# ASCII_06_LMS7002M_RF2.net
KiCad netlist of a schematic drawn in Altium Designer
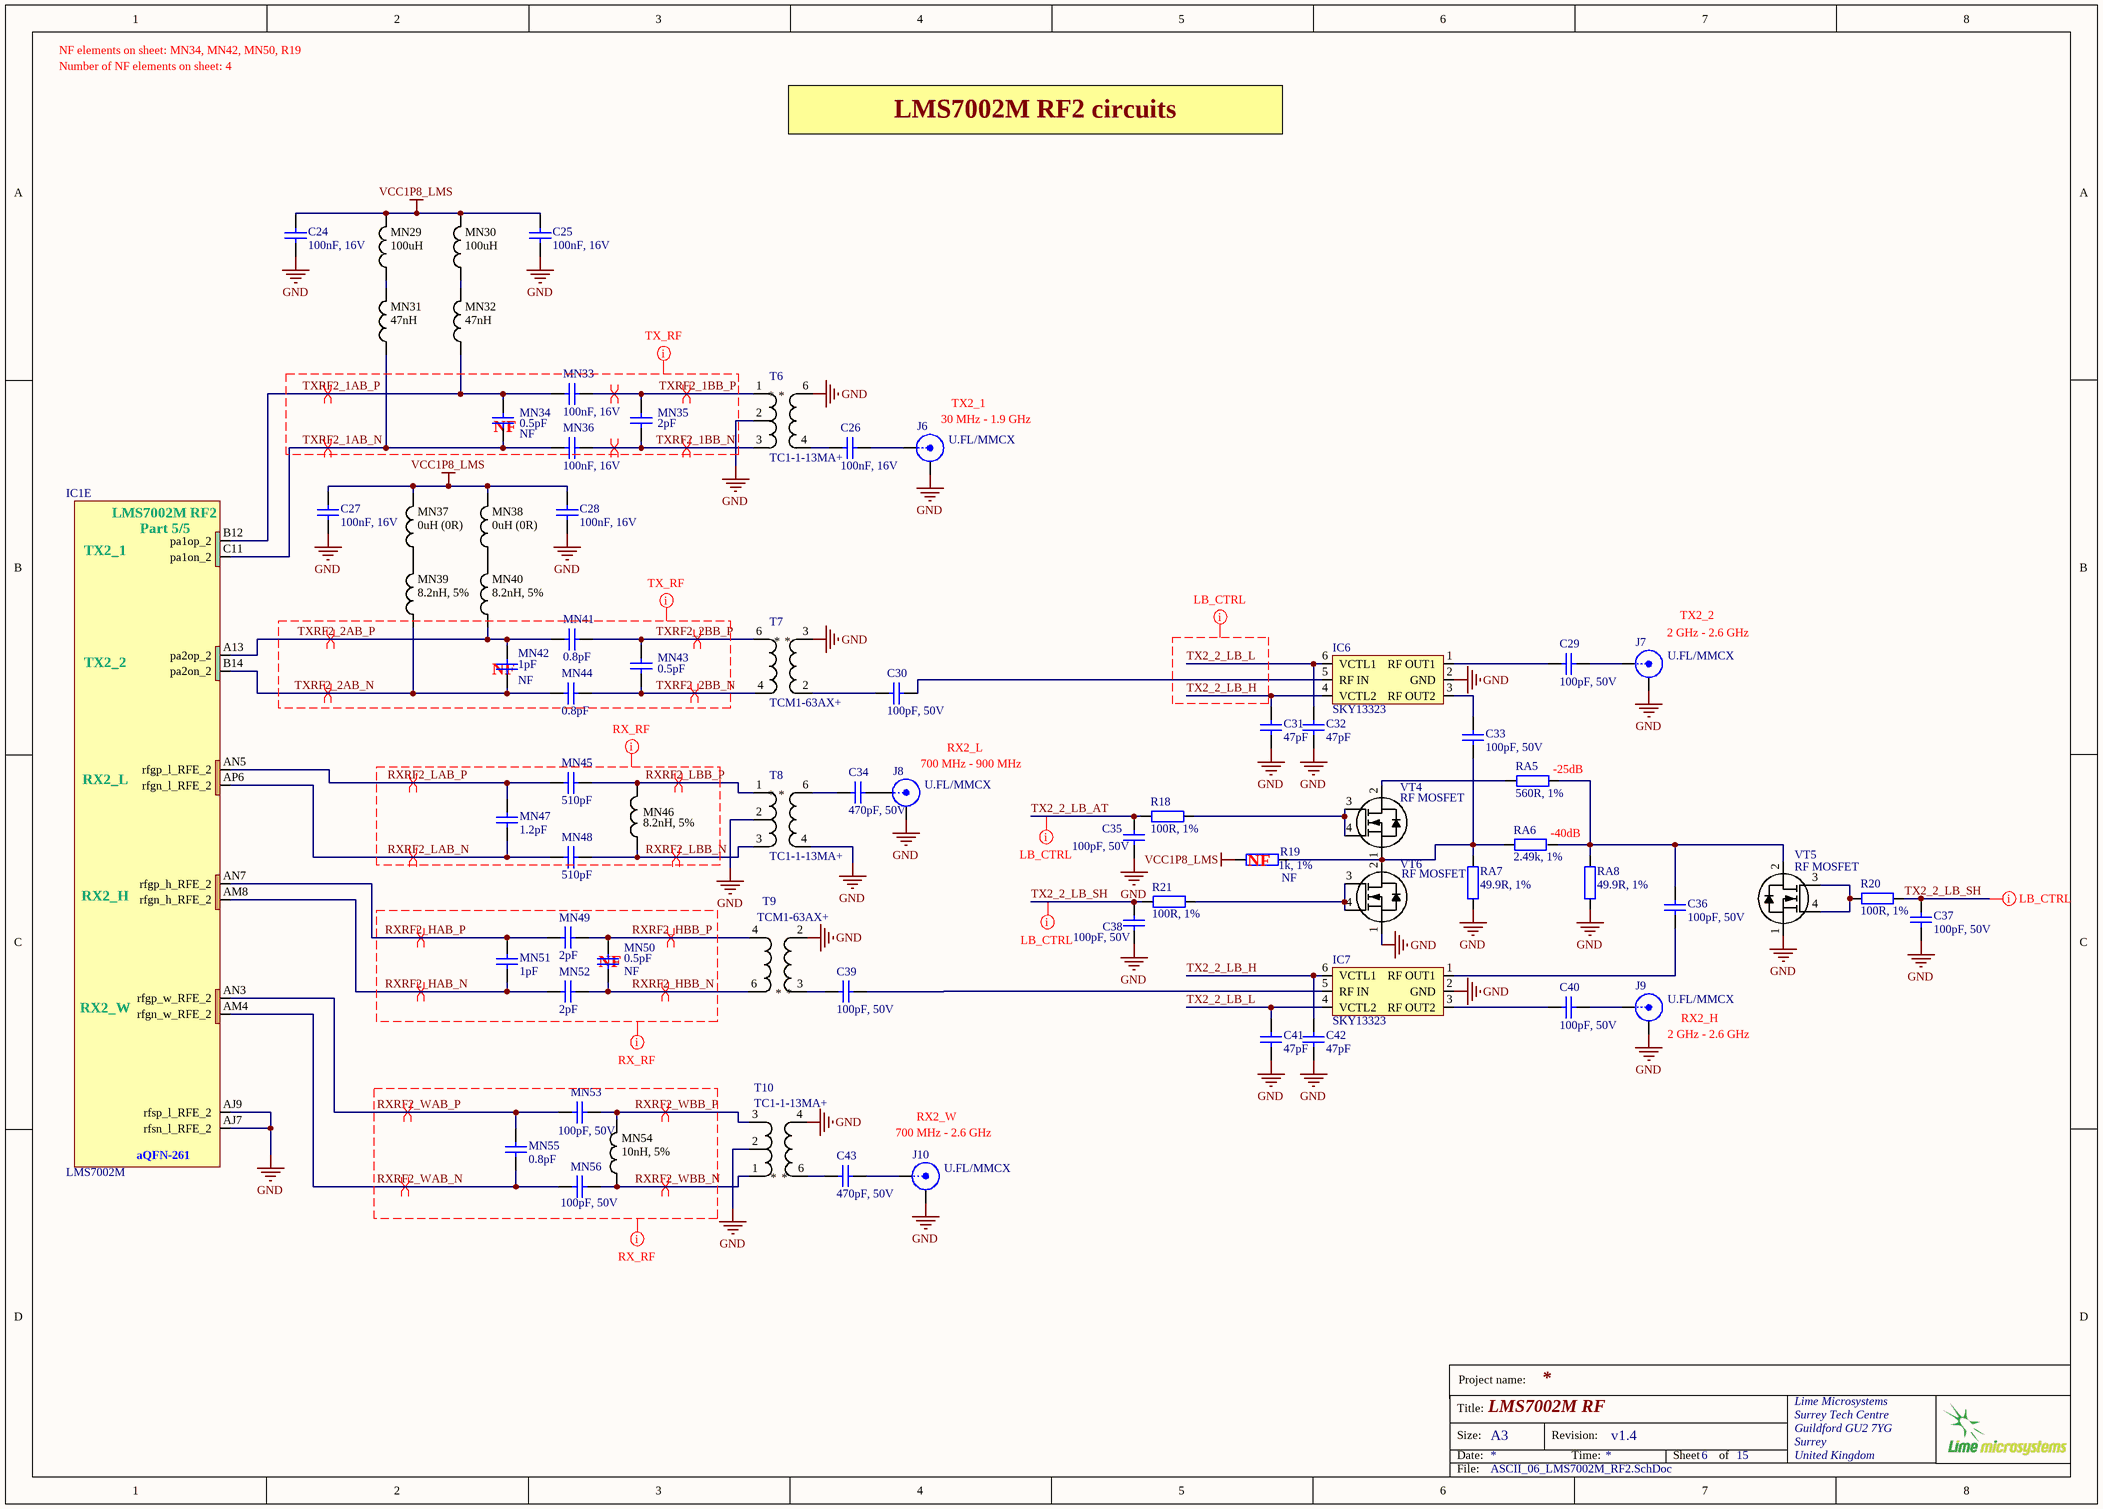
[diagram p0: ASCII_06_LMS7002M_RF2.SchDoc]

(export (version "E")
  (design (tool "Eeschema 10.0.6"))
  (components
    (comp (ref "C24")
      (value "100nF, 16V")
      (footprint "CAP0402")
      (fields
        (field (name "MANUFACTURER") "Murata Electronics")
        (field (name "TOLERANCE") "10 %")
        (field (name "MANUFACTURER PART NUMBER") "GRM155R71C104KA88D")
      )
      (libsource (lib "LimeMicroAltiumLib_schLib") (part "Cap_0402"))
    )
    (comp (ref "C25")
      (value "100nF, 16V")
      (footprint "CAP0402")
      (fields
        (field (name "MANUFACTURER") "Murata Electronics")
        (field (name "TOLERANCE") "10 %")
        (field (name "MANUFACTURER PART NUMBER") "GRM155R71C104KA88D")
      )
      (libsource (lib "LimeMicroAltiumLib_schLib") (part "Cap_0402"))
    )
    (comp (ref "C26")
      (value "100nF, 16V")
      (footprint "CAP0402")
      (fields
        (field (name "MANUFACTURER") "Murata Electronics")
        (field (name "TOLERANCE") "10 %")
        (field (name "MANUFACTURER PART NUMBER") "GRM155R71C104KA88D")
      )
      (libsource (lib "LimeMicroAltiumLib_schLib") (part "Cap_0402"))
    )
    (comp (ref "C27")
      (value "100nF, 16V")
      (footprint "CAP0402")
      (fields
        (field (name "MANUFACTURER") "Murata Electronics")
        (field (name "TOLERANCE") "10 %")
        (field (name "MANUFACTURER PART NUMBER") "GRM155R71C104KA88D")
      )
      (libsource (lib "LimeMicroAltiumLib_schLib") (part "Cap_0402"))
    )
    (comp (ref "C28")
      (value "100nF, 16V")
      (footprint "CAP0402")
      (fields
        (field (name "MANUFACTURER") "Murata Electronics")
        (field (name "TOLERANCE") "10 %")
        (field (name "MANUFACTURER PART NUMBER") "GRM155R71C104KA88D")
      )
      (libsource (lib "LimeMicroAltiumLib_schLib") (part "Cap_0402"))
    )
    (comp (ref "C29")
      (value "100pF, 50V")
      (footprint "CAP0402")
      (fields (field (name "TOLERANCE") "±5%") (field (name "MANUFACTURER") "Yageo"))
      (libsource (lib "LimeMicroAltiumLib_schLib") (part "Cap_0402"))
    )
    (comp (ref "C30")
      (value "100pF, 50V")
      (footprint "CAP0402")
      (fields (field (name "TOLERANCE") "±5%") (field (name "MANUFACTURER") "Yageo"))
      (libsource (lib "LimeMicroAltiumLib_schLib") (part "Cap_0402"))
    )
    (comp (ref "C31")
      (value "47pF")
      (footprint "CAP0402")
      (fields (field (name "TOLERANCE") "±1%") (field (name "MANUFACTURER") "TDK Corporation"))
      (libsource (lib "LimeMicroAltiumLib_schLib") (part "Cap_0402"))
    )
    (comp (ref "C32")
      (value "47pF")
      (footprint "CAP0402")
      (fields (field (name "TOLERANCE") "±1%") (field (name "MANUFACTURER") "TDK Corporation"))
      (libsource (lib "LimeMicroAltiumLib_schLib") (part "Cap_0402"))
    )
    (comp (ref "C33")
      (value "100pF, 50V")
      (footprint "CAP0402")
      (fields (field (name "TOLERANCE") "±5%") (field (name "MANUFACTURER") "Yageo"))
      (libsource (lib "LimeMicroAltiumLib_schLib") (part "Cap_0402"))
    )
    (comp (ref "C34")
      (value "470pF, 50V")
      (footprint "CAP0402")
      (fields
        (field (name "MANUFACTURER PART NUMBER") "C1005C0G1H471J050BA")
        (field (name "TOLERANCE") "±5%")
        (field (name "MANUFACTURER") "TDK Corporation")
      )
      (libsource (lib "LimeMicroAltiumLib_schLib") (part "Cap_0402"))
    )
    (comp (ref "C35")
      (value "100pF, 50V")
      (footprint "CAP0402")
      (fields (field (name "TOLERANCE") "±5%") (field (name "MANUFACTURER") "Yageo"))
      (libsource (lib "LimeMicroAltiumLib_schLib") (part "Cap_0402"))
    )
    (comp (ref "C36")
      (value "100pF, 50V")
      (footprint "CAP0402")
      (fields (field (name "TOLERANCE") "±5%") (field (name "MANUFACTURER") "Yageo"))
      (libsource (lib "LimeMicroAltiumLib_schLib") (part "Cap_0402"))
    )
    (comp (ref "C37")
      (value "100pF, 50V")
      (footprint "CAP0402")
      (fields (field (name "TOLERANCE") "±5%") (field (name "MANUFACTURER") "Yageo"))
      (libsource (lib "LimeMicroAltiumLib_schLib") (part "Cap_0402"))
    )
    (comp (ref "C38")
      (value "100pF, 50V")
      (footprint "CAP0402")
      (fields (field (name "TOLERANCE") "±5%") (field (name "MANUFACTURER") "Yageo"))
      (libsource (lib "LimeMicroAltiumLib_schLib") (part "Cap_0402"))
    )
    (comp (ref "C39")
      (value "100pF, 50V")
      (footprint "CAP0402")
      (fields (field (name "TOLERANCE") "±5%") (field (name "MANUFACTURER") "Yageo"))
      (libsource (lib "LimeMicroAltiumLib_schLib") (part "Cap_0402"))
    )
    (comp (ref "C40")
      (value "100pF, 50V")
      (footprint "CAP0402")
      (fields (field (name "TOLERANCE") "±5%") (field (name "MANUFACTURER") "Yageo"))
      (libsource (lib "LimeMicroAltiumLib_schLib") (part "Cap_0402"))
    )
    (comp (ref "C41")
      (value "47pF")
      (footprint "CAP0402")
      (fields (field (name "TOLERANCE") "±1%") (field (name "MANUFACTURER") "TDK Corporation"))
      (libsource (lib "LimeMicroAltiumLib_schLib") (part "Cap_0402"))
    )
    (comp (ref "C42")
      (value "47pF")
      (footprint "CAP0402")
      (fields (field (name "TOLERANCE") "±1%") (field (name "MANUFACTURER") "TDK Corporation"))
      (libsource (lib "LimeMicroAltiumLib_schLib") (part "Cap_0402"))
    )
    (comp (ref "C43")
      (value "470pF, 50V")
      (footprint "CAP0402")
      (fields
        (field (name "MANUFACTURER PART NUMBER") "C1005C0G1H471J050BA")
        (field (name "TOLERANCE") "±5%")
        (field (name "MANUFACTURER") "TDK Corporation")
      )
      (libsource (lib "LimeMicroAltiumLib_schLib") (part "Cap_0402"))
    )
    (comp (ref "IC1")
      (value "LMS7002M")
      (footprint "LMS7002M_v3")
      (fields (field (name "MANUFACTURER") "Lime Microsystems"))
      (libsource (lib "LimeMicroAltiumLib_schLib") (part "LMS7002M"))
    )
    (comp (ref "IC6")
      (value "SKY13323")
      (footprint "SKY13323-378LF")
      (description "SKY13323-378LF: 0.1-3.0 GHz GaAs SPDT Switch")
      (fields (field (name "MANUFACTURER") "Skyworks Solutions Inc."))
      (libsource (lib "LimeMicroAltiumLib_schLib") (part "SKY13323"))
    )
    (comp (ref "IC7")
      (value "SKY13323")
      (footprint "SKY13323-378LF")
      (description "SKY13323-378LF: 0.1-3.0 GHz GaAs SPDT Switch")
      (fields (field (name "MANUFACTURER") "Skyworks Solutions Inc."))
      (libsource (lib "LimeMicroAltiumLib_schLib") (part "SKY13323"))
    )
    (comp (ref "J6")
      (value "U.FL/MMCX")
      (footprint "MMCX_UFL_conn_u")
      (description "CONN UMC RCPT STR 50 OHM SMD")
      (fields (field (name "MANUFACTURER") "Molex, LLC"))
      (libsource (lib "LimeMicroAltiumLib_schLib") (part "RF_IF_connector"))
    )
    (comp (ref "J7")
      (value "U.FL/MMCX")
      (footprint "MMCX_UFL_conn_u")
      (description "CONN UMC RCPT STR 50 OHM SMD")
      (fields (field (name "MANUFACTURER") "Molex, LLC"))
      (libsource (lib "LimeMicroAltiumLib_schLib") (part "RF_IF_connector"))
    )
    (comp (ref "J8")
      (value "U.FL/MMCX")
      (footprint "MMCX_UFL_conn_u")
      (description "CONN UMC RCPT STR 50 OHM SMD")
      (fields (field (name "MANUFACTURER") "Molex, LLC"))
      (libsource (lib "LimeMicroAltiumLib_schLib") (part "RF_IF_connector"))
    )
    (comp (ref "J9")
      (value "U.FL/MMCX")
      (footprint "MMCX_UFL_conn_u")
      (description "CONN UMC RCPT STR 50 OHM SMD")
      (fields (field (name "MANUFACTURER") "Molex, LLC"))
      (libsource (lib "LimeMicroAltiumLib_schLib") (part "RF_IF_connector"))
    )
    (comp (ref "J10")
      (value "U.FL/MMCX")
      (footprint "MMCX_UFL_conn_u")
      (description "CONN UMC RCPT STR 50 OHM SMD")
      (fields (field (name "MANUFACTURER") "Molex, LLC"))
      (libsource (lib "LimeMicroAltiumLib_schLib") (part "RF_IF_connector"))
    )
    (comp (ref "MN29")
      (value "100uH")
      (footprint "RES0805")
      (fields
        (field (name "TOLERANCE") "±10%")
        (field (name "MANUFACTURER") "TDK Corporation")
        (field (name "MANUFACTURER PART NUMBER") "MLF2012C101KT000")
      )
      (libsource (lib "LimeMicroAltiumLib_schLib") (part "Inductor_0603"))
    )
    (comp (ref "MN30")
      (value "100uH")
      (footprint "RES0805")
      (fields
        (field (name "TOLERANCE") "±10%")
        (field (name "MANUFACTURER") "TDK Corporation")
        (field (name "MANUFACTURER PART NUMBER") "MLF2012C101KT000")
      )
      (libsource (lib "LimeMicroAltiumLib_schLib") (part "Inductor_0603"))
    )
    (comp (ref "MN31")
      (value "47nH")
      (footprint "RES0402")
      (fields
        (field (name "MANUFACTURER") "COILCRAFT")
        (field (name "MANUFACTURER PART NUMBER") "0402HP-47NXJLU")
      )
      (libsource (lib "LimeMicroAltiumLib_schLib") (part "Inductor_0603"))
    )
    (comp (ref "MN32")
      (value "47nH")
      (footprint "RES0402")
      (fields
        (field (name "MANUFACTURER") "COILCRAFT")
        (field (name "MANUFACTURER PART NUMBER") "0402HP-47NXJLU")
      )
      (libsource (lib "LimeMicroAltiumLib_schLib") (part "Inductor_0603"))
    )
    (comp (ref "MN33")
      (value "100nF, 16V")
      (footprint "CAP0402")
      (fields
        (field (name "MANUFACTURER") "Murata Electronics")
        (field (name "TOLERANCE") "10 %")
        (field (name "MANUFACTURER PART NUMBER") "GRM155R71C104KA88D")
      )
      (libsource (lib "LimeMicroAltiumLib_schLib") (part "Cap_0402"))
    )
    (comp (ref "MN34")
      (value "0.5pF")
      (footprint "CAP0402")
      (fields
        (field (name "ASSEMBLY INFO") "NF")
        (field (name "TOLERANCE") "±0.25pF")
        (field (name "MANUFACTURER") "Yageo")
      )
      (libsource (lib "LimeMicroAltiumLib_schLib") (part "Cap_0402"))
    )
    (comp (ref "MN35")
      (value "2pF")
      (footprint "CAP0402")
      (fields (field (name "MANUFACTURER PART NUMBER") "04025U2R0BAT2A") (field (name "MANUFACTURER") "AVX"))
      (libsource (lib "LimeMicroAltiumLib_schLib") (part "Cap_0402"))
    )
    (comp (ref "MN36")
      (value "100nF, 16V")
      (footprint "CAP0402")
      (fields
        (field (name "MANUFACTURER") "Murata Electronics")
        (field (name "TOLERANCE") "10 %")
        (field (name "MANUFACTURER PART NUMBER") "GRM155R71C104KA88D")
      )
      (libsource (lib "LimeMicroAltiumLib_schLib") (part "Cap_0402"))
    )
    (comp (ref "MN37")
      (value "0uH (0R)")
      (footprint "RES0805")
      (fields (field (name "MANUFACTURER") "BOURNS"))
      (libsource (lib "LimeMicroAltiumLib_schLib") (part "Inductor_0603"))
    )
    (comp (ref "MN38")
      (value "0uH (0R)")
      (footprint "RES0805")
      (fields (field (name "MANUFACTURER") "BOURNS"))
      (libsource (lib "LimeMicroAltiumLib_schLib") (part "Inductor_0603"))
    )
    (comp (ref "MN39")
      (value "8.2nH, 5%")
      (footprint "RES0402")
      (fields (field (name "MANUFACTURER") "COILCRAFT"))
      (libsource (lib "LimeMicroAltiumLib_schLib") (part "Inductor_0603"))
    )
    (comp (ref "MN40")
      (value "8.2nH, 5%")
      (footprint "RES0402")
      (fields (field (name "MANUFACTURER") "COILCRAFT"))
      (libsource (lib "LimeMicroAltiumLib_schLib") (part "Inductor_0603"))
    )
    (comp (ref "MN41")
      (value "0.8pF")
      (footprint "CAP0402")
      (fields
        (field (name "TOLERANCE") "±0.1pF")
        (field (name "MANUFACTURER") "Murata Electronics North America")
        (field (name "MANUFACTURER PART NUMBER") "GRM1555C1HR80BA01D")
      )
      (libsource (lib "LimeMicroAltiumLib_schLib") (part "Cap_0402"))
    )
    (comp (ref "MN42")
      (value "1pF")
      (footprint "CAP0402")
      (fields
        (field (name "ASSEMBLY INFO") "NF")
        (field (name "MANUFACTURER") "TDK Corporation")
        (field (name "TOLERANCE") "±0.1pF")
      )
      (libsource (lib "LimeMicroAltiumLib_schLib") (part "Cap_0402"))
    )
    (comp (ref "MN43")
      (value "0.5pF")
      (footprint "CAP0402")
      (fields (field (name "TOLERANCE") "±0.25pF") (field (name "MANUFACTURER") "Yageo"))
      (libsource (lib "LimeMicroAltiumLib_schLib") (part "Cap_0402"))
    )
    (comp (ref "MN44")
      (value "0.8pF")
      (footprint "CAP0402")
      (fields
        (field (name "TOLERANCE") "±0.1pF")
        (field (name "MANUFACTURER") "Murata Electronics North America")
        (field (name "MANUFACTURER PART NUMBER") "GRM1555C1HR80BA01D")
      )
      (libsource (lib "LimeMicroAltiumLib_schLib") (part "Cap_0402"))
    )
    (comp (ref "MN45")
      (value "510pF")
      (footprint "CAP0402")
      (fields
        (field (name "TOLERANCE") "±5%")
        (field (name "MANUFACTURER") "Murata Electronics North America")
        (field (name "MANUFACTURER PART NUMBER") "GRM1555C1H511JA01D")
      )
      (libsource (lib "LimeMicroAltiumLib_schLib") (part "Cap_0402"))
    )
    (comp (ref "MN46")
      (value "8.2nH, 5%")
      (footprint "RES0402")
      (fields (field (name "MANUFACTURER") "COILCRAFT"))
      (libsource (lib "LimeMicroAltiumLib_schLib") (part "Inductor_0603"))
    )
    (comp (ref "MN47")
      (value "1.2pF")
      (footprint "CAP0402")
      (fields
        (field (name "MANUFACTURER") "Murata Electronics North America")
        (field (name "MANUFACTURER PART NUMBER") "GRM1555C1H1R2CA01D")
        (field (name "TOLERANCE") "±0.25pF")
      )
      (libsource (lib "LimeMicroAltiumLib_schLib") (part "Cap_0402"))
    )
    (comp (ref "MN48")
      (value "510pF")
      (footprint "CAP0402")
      (fields
        (field (name "TOLERANCE") "±5%")
        (field (name "MANUFACTURER") "Murata Electronics North America")
        (field (name "MANUFACTURER PART NUMBER") "GRM1555C1H511JA01D")
      )
      (libsource (lib "LimeMicroAltiumLib_schLib") (part "Cap_0402"))
    )
    (comp (ref "MN49")
      (value "2pF")
      (footprint "CAP0402")
      (fields (field (name "MANUFACTURER PART NUMBER") "04025U2R0BAT2A") (field (name "MANUFACTURER") "AVX"))
      (libsource (lib "LimeMicroAltiumLib_schLib") (part "Cap_0402"))
    )
    (comp (ref "MN50")
      (value "0.5pF")
      (footprint "CAP0402")
      (fields
        (field (name "ASSEMBLY INFO") "NF")
        (field (name "TOLERANCE") "±0.25pF")
        (field (name "MANUFACTURER") "Yageo")
      )
      (libsource (lib "LimeMicroAltiumLib_schLib") (part "Cap_0402"))
    )
    (comp (ref "MN51")
      (value "1pF")
      (footprint "CAP0402")
      (fields (field (name "MANUFACTURER") "TDK Corporation") (field (name "TOLERANCE") "±0.1pF"))
      (libsource (lib "LimeMicroAltiumLib_schLib") (part "Cap_0402"))
    )
    (comp (ref "MN52")
      (value "2pF")
      (footprint "CAP0402")
      (fields (field (name "MANUFACTURER PART NUMBER") "04025U2R0BAT2A") (field (name "MANUFACTURER") "AVX"))
      (libsource (lib "LimeMicroAltiumLib_schLib") (part "Cap_0402"))
    )
    (comp (ref "MN53")
      (value "100pF, 50V")
      (footprint "CAP0402")
      (fields (field (name "TOLERANCE") "±5%") (field (name "MANUFACTURER") "Yageo"))
      (libsource (lib "LimeMicroAltiumLib_schLib") (part "Cap_0402"))
    )
    (comp (ref "MN54")
      (value "10nH, 5%")
      (footprint "RES0402")
      (fields (field (name "MANUFACTURER") "COILCRAFT"))
      (libsource (lib "LimeMicroAltiumLib_schLib") (part "Inductor_0603"))
    )
    (comp (ref "MN55")
      (value "0.8pF")
      (footprint "CAP0402")
      (fields
        (field (name "TOLERANCE") "±0.1pF")
        (field (name "MANUFACTURER") "Murata Electronics North America")
        (field (name "MANUFACTURER PART NUMBER") "GRM1555C1HR80BA01D")
      )
      (libsource (lib "LimeMicroAltiumLib_schLib") (part "Cap_0402"))
    )
    (comp (ref "MN56")
      (value "100pF, 50V")
      (footprint "CAP0402")
      (fields (field (name "TOLERANCE") "±5%") (field (name "MANUFACTURER") "Yageo"))
      (libsource (lib "LimeMicroAltiumLib_schLib") (part "Cap_0402"))
    )
    (comp (ref "R18")
      (value "100R, 1%")
      (footprint "RES0402")
      (fields (field (name "TOLERANCE") "±1%") (field (name "MANUFACTURER") "Stackpole Electronics Inc."))
      (libsource (lib "LimeFPGAboard_schLib") (part "Res_0402"))
    )
    (comp (ref "R19")
      (value "1k, 1%")
      (footprint "RES0402")
      (fields
        (field (name "ASSEMBLY INFO") "NF")
        (field (name "MANUFACTURER") "Stackpole Electronics Inc")
        (field (name "TOLERANCE") "±1%")
      )
      (libsource (lib "LimeMicroAltiumLib_schLib") (part "Res_0402"))
    )
    (comp (ref "R20")
      (value "100R, 1%")
      (footprint "RES0402")
      (fields (field (name "TOLERANCE") "±1%") (field (name "MANUFACTURER") "Stackpole Electronics Inc."))
      (libsource (lib "LimeFPGAboard_schLib") (part "Res_0402"))
    )
    (comp (ref "R21")
      (value "100R, 1%")
      (footprint "RES0402")
      (fields (field (name "TOLERANCE") "±1%") (field (name "MANUFACTURER") "Stackpole Electronics Inc."))
      (libsource (lib "LimeFPGAboard_schLib") (part "Res_0402"))
    )
    (comp (ref "RA5")
      (value "560R, 1%")
      (footprint "RES0402")
      (fields
        (field (name "MANUFACTURER PART NUMBER") "CRCW0402560RFKED")
        (field (name "TOLERANCE") "±1%")
        (field (name "MANUFACTURER") "Vishay Dale")
      )
      (libsource (lib "LimeMicroAltiumLib_schLib") (part "Res_0402"))
    )
    (comp (ref "RA6")
      (value "2.49k, 1%")
      (footprint "RES0402")
      (fields
        (field (name "TOLERANCE") "±1%")
        (field (name "MANUFACTURER PART NUMBER") "RC0402FR-072K49L")
        (field (name "MANUFACTURER") "Yageo")
      )
      (libsource (lib "LimeMicroAltiumLib_schLib") (part "Res_0402"))
    )
    (comp (ref "RA7")
      (value "49.9R, 1%")
      (footprint "RES0402")
      (fields
        (field (name "TOLERANCE") "±1%")
        (field (name "MANUFACTURER") "Samsung Electro-Mechanics America, Inc.")
        (field (name "MANUFACTURER PART NUMBER") "RC1005F49R9CS")
      )
      (libsource (lib "LimeMicroAltiumLib_schLib") (part "Res_0402"))
    )
    (comp (ref "RA8")
      (value "49.9R, 1%")
      (footprint "RES0402")
      (fields
        (field (name "TOLERANCE") "±1%")
        (field (name "MANUFACTURER") "Samsung Electro-Mechanics America, Inc.")
        (field (name "MANUFACTURER PART NUMBER") "RC1005F49R9CS")
      )
      (libsource (lib "LimeMicroAltiumLib_schLib") (part "Res_0402"))
    )
    (comp (ref "T6")
      (value "TC1-1-13MA+")
      (footprint "TC1-1-13MA+_v2")
      (fields (field (name "MANUFACTURER") "Mini-Circuits"))
      (libsource (lib "LimeMicroAltiumLib_schLib") (part "Balun"))
    )
    (comp (ref "T7")
      (value "TCM1-63AX+")
      (footprint "TCM1-63AX+_v2")
      (fields (field (name "MANUFACTURER") "Mini-circuits"))
      (libsource (lib "LimeMicroAltiumLib_schLib") (part "Balun_v2"))
    )
    (comp (ref "T8")
      (value "TC1-1-13MA+")
      (footprint "TC1-1-13MA+_v2")
      (fields (field (name "MANUFACTURER") "Mini-Circuits"))
      (libsource (lib "LimeMicroAltiumLib_schLib") (part "Balun"))
    )
    (comp (ref "T9")
      (value "TCM1-63AX+")
      (footprint "TCM1-63AX+_v2")
      (fields (field (name "MANUFACTURER") "Mini-circuits"))
      (libsource (lib "") (part "Balun_v2_1"))
    )
    (comp (ref "T10")
      (value "TC1-1-13MA+")
      (footprint "TC1-1-13MA+_v2")
      (fields (field (name "MANUFACTURER") "Mini-Circuits"))
      (libsource (lib "") (part "Balun_1"))
    )
    (comp (ref "VT4")
      (value "RF MOSFET")
      (footprint "BF1105R_SOT143R4")
      (fields (field (name "MANUFACTURER") "NXP Semiconductors"))
      (libsource (lib "LimeMicroAltiumLib_schLib") (part "BF1105R,215"))
    )
    (comp (ref "VT5")
      (value "RF MOSFET")
      (footprint "BF1105R_SOT143R4")
      (fields (field (name "MANUFACTURER") "NXP Semiconductors"))
      (libsource (lib "LimeMicroAltiumLib_schLib") (part "BF1105R,215"))
    )
    (comp (ref "VT6")
      (value "RF MOSFET")
      (footprint "BF1105R_SOT143R4")
      (fields (field (name "MANUFACTURER") "NXP Semiconductors"))
      (libsource (lib "LimeMicroAltiumLib_schLib") (part "BF1105R,215"))
    )
  )
  (nets
    (net (code "1") (name "/RXRF2_HAB_N") (class "Default")
      (node (ref "IC1") (pin "AM8") (pinfunction "rfgn_h_RFE_2_AM8") (pintype "passive"))
      (node (ref "MN51") (pin "1") (pinfunction "1_1") (pintype "passive"))
      (node (ref "MN52") (pin "2") (pinfunction "2_2") (pintype "passive"))
    )
    (net (code "2") (name "/RXRF2_HAB_P") (class "Default")
      (node (ref "IC1") (pin "AN7") (pinfunction "rfgp_h_RFE_2_AN7") (pintype "passive"))
      (node (ref "MN49") (pin "2") (pinfunction "2_2") (pintype "passive"))
      (node (ref "MN51") (pin "2") (pinfunction "2_2") (pintype "passive"))
    )
    (net (code "3") (name "/RXRF2_HBB_N") (class "Default")
      (node (ref "MN50") (pin "1") (pinfunction "1_1") (pintype "passive"))
      (node (ref "MN52") (pin "1") (pinfunction "1_1") (pintype "passive"))
      (node (ref "T9") (pin "6") (pinfunction "6_6") (pintype "passive"))
    )
    (net (code "4") (name "/RXRF2_HBB_P") (class "Default")
      (node (ref "MN49") (pin "1") (pinfunction "1_1") (pintype "passive"))
      (node (ref "MN50") (pin "2") (pinfunction "2_2") (pintype "passive"))
      (node (ref "T9") (pin "4") (pinfunction "4_4") (pintype "passive"))
    )
    (net (code "5") (name "/RXRF2_LAB_N") (class "Default")
      (node (ref "IC1") (pin "AP6") (pinfunction "rfgn_l_RFE_2_AP6") (pintype "passive"))
      (node (ref "MN47") (pin "1") (pinfunction "1_1") (pintype "passive"))
      (node (ref "MN48") (pin "2") (pinfunction "2_2") (pintype "passive"))
    )
    (net (code "6") (name "/RXRF2_LAB_P") (class "Default")
      (node (ref "IC1") (pin "AN5") (pinfunction "rfgp_l_RFE_2_AN5") (pintype "passive"))
      (node (ref "MN45") (pin "2") (pinfunction "2_2") (pintype "passive"))
      (node (ref "MN47") (pin "2") (pinfunction "2_2") (pintype "passive"))
    )
    (net (code "7") (name "/RXRF2_LBB_N") (class "Default")
      (node (ref "MN46") (pin "1") (pinfunction "1_1") (pintype "passive"))
      (node (ref "MN48") (pin "1") (pinfunction "1_1") (pintype "passive"))
      (node (ref "T8") (pin "3") (pinfunction "3_3") (pintype "passive"))
    )
    (net (code "8") (name "/RXRF2_LBB_P") (class "Default")
      (node (ref "MN45") (pin "1") (pinfunction "1_1") (pintype "passive"))
      (node (ref "MN46") (pin "2") (pinfunction "2_2") (pintype "passive"))
      (node (ref "T8") (pin "1") (pinfunction "1_1") (pintype "passive"))
    )
    (net (code "9") (name "/RXRF2_WAB_N") (class "Default")
      (node (ref "IC1") (pin "AM4") (pinfunction "rfgn_w_RFE_2_AM4") (pintype "passive"))
      (node (ref "MN55") (pin "2") (pinfunction "2_2") (pintype "passive"))
      (node (ref "MN56") (pin "2") (pinfunction "2_2") (pintype "passive"))
    )
    (net (code "10") (name "/RXRF2_WAB_P") (class "Default")
      (node (ref "IC1") (pin "AN3") (pinfunction "rfgp_w_RFE_2_AN3") (pintype "passive"))
      (node (ref "MN53") (pin "2") (pinfunction "2_2") (pintype "passive"))
      (node (ref "MN55") (pin "1") (pinfunction "1_1") (pintype "passive"))
    )
    (net (code "11") (name "/RXRF2_WBB_N") (class "Default")
      (node (ref "MN54") (pin "1") (pinfunction "1_1") (pintype "passive"))
      (node (ref "MN56") (pin "1") (pinfunction "1_1") (pintype "passive"))
      (node (ref "T10") (pin "1") (pinfunction "1_1") (pintype "passive"))
    )
    (net (code "12") (name "/RXRF2_WBB_P") (class "Default")
      (node (ref "MN53") (pin "1") (pinfunction "1_1") (pintype "passive"))
      (node (ref "MN54") (pin "2") (pinfunction "2_2") (pintype "passive"))
      (node (ref "T10") (pin "3") (pinfunction "3_3") (pintype "passive"))
    )
    (net (code "13") (name "/TX2_2_LB_AT") (class "Default")
      (node (ref "C35") (pin "1") (pinfunction "1_1") (pintype "passive"))
      (node (ref "R18") (pin "2") (pinfunction "2_2") (pintype "passive"))
    )
    (net (code "14") (name "/TX2_2_LB_H") (class "Default")
      (node (ref "C31") (pin "2") (pinfunction "2_2") (pintype "passive"))
      (node (ref "C42") (pin "2") (pinfunction "2_2") (pintype "passive"))
      (node (ref "IC6") (pin "4") (pinfunction "VCTL2_4") (pintype "input"))
      (node (ref "IC7") (pin "6") (pinfunction "VCTL1_6") (pintype "input"))
    )
    (net (code "15") (name "/TX2_2_LB_L") (class "Default")
      (node (ref "C32") (pin "2") (pinfunction "2_2") (pintype "passive"))
      (node (ref "C41") (pin "2") (pinfunction "2_2") (pintype "passive"))
      (node (ref "IC6") (pin "6") (pinfunction "VCTL1_6") (pintype "input"))
      (node (ref "IC7") (pin "4") (pinfunction "VCTL2_4") (pintype "input"))
    )
    (net (code "16") (name "/TX2_2_LB_SH") (class "Default")
      (node (ref "C37") (pin "1") (pinfunction "1_1") (pintype "passive"))
      (node (ref "C38") (pin "1") (pinfunction "1_1") (pintype "passive"))
      (node (ref "R20") (pin "1") (pinfunction "1_1") (pintype "passive"))
      (node (ref "R21") (pin "2") (pinfunction "2_2") (pintype "passive"))
    )
    (net (code "17") (name "/TXRF2_1AB_N") (class "Default")
      (node (ref "IC1") (pin "C11") (pinfunction "pa1on_2_C11") (pintype "passive"))
      (node (ref "MN31") (pin "1") (pinfunction "1_1") (pintype "passive"))
      (node (ref "MN34") (pin "1") (pinfunction "1_1") (pintype "passive"))
      (node (ref "MN36") (pin "1") (pinfunction "1_1") (pintype "passive"))
    )
    (net (code "18") (name "/TXRF2_1AB_P") (class "Default")
      (node (ref "IC1") (pin "B12") (pinfunction "pa1op_2_B12") (pintype "passive"))
      (node (ref "MN32") (pin "1") (pinfunction "1_1") (pintype "passive"))
      (node (ref "MN33") (pin "2") (pinfunction "2_2") (pintype "passive"))
      (node (ref "MN34") (pin "2") (pinfunction "2_2") (pintype "passive"))
    )
    (net (code "19") (name "/TXRF2_1BB_N") (class "Default")
      (node (ref "MN35") (pin "1") (pinfunction "1_1") (pintype "passive"))
      (node (ref "MN36") (pin "2") (pinfunction "2_2") (pintype "passive"))
      (node (ref "T6") (pin "3") (pinfunction "3_3") (pintype "passive"))
    )
    (net (code "20") (name "/TXRF2_1BB_P") (class "Default")
      (node (ref "MN33") (pin "1") (pinfunction "1_1") (pintype "passive"))
      (node (ref "MN35") (pin "2") (pinfunction "2_2") (pintype "passive"))
      (node (ref "T6") (pin "1") (pinfunction "1_1") (pintype "passive"))
    )
    (net (code "21") (name "/TXRF2_2AB_N") (class "Default")
      (node (ref "IC1") (pin "B14") (pinfunction "pa2on_2_B14") (pintype "passive"))
      (node (ref "MN39") (pin "1") (pinfunction "1_1") (pintype "passive"))
      (node (ref "MN42") (pin "2") (pinfunction "2_2") (pintype "passive"))
      (node (ref "MN44") (pin "2") (pinfunction "2_2") (pintype "passive"))
    )
    (net (code "22") (name "/TXRF2_2AB_P") (class "Default")
      (node (ref "IC1") (pin "A13") (pinfunction "pa2op_2_A13") (pintype "passive"))
      (node (ref "MN40") (pin "1") (pinfunction "1_1") (pintype "passive"))
      (node (ref "MN41") (pin "2") (pinfunction "2_2") (pintype "passive"))
      (node (ref "MN42") (pin "1") (pinfunction "1_1") (pintype "passive"))
    )
    (net (code "23") (name "/TXRF2_2BB_N") (class "Default")
      (node (ref "MN43") (pin "1") (pinfunction "1_1") (pintype "passive"))
      (node (ref "MN44") (pin "1") (pinfunction "1_1") (pintype "passive"))
      (node (ref "T7") (pin "4") (pinfunction "4_4") (pintype "passive"))
    )
    (net (code "24") (name "/TXRF2_2BB_P") (class "Default")
      (node (ref "MN41") (pin "1") (pinfunction "1_1") (pintype "passive"))
      (node (ref "MN43") (pin "2") (pinfunction "2_2") (pintype "passive"))
      (node (ref "T7") (pin "6") (pinfunction "6_6") (pintype "passive"))
    )
    (net (code "25") (name "GND") (class "Default")
      (node (ref "C24") (pin "1") (pinfunction "1_1") (pintype "passive"))
      (node (ref "C25") (pin "1") (pinfunction "1_1") (pintype "passive"))
      (node (ref "C27") (pin "1") (pinfunction "1_1") (pintype "passive"))
      (node (ref "C28") (pin "1") (pinfunction "1_1") (pintype "passive"))
      (node (ref "C31") (pin "1") (pinfunction "1_1") (pintype "passive"))
      (node (ref "C32") (pin "1") (pinfunction "1_1") (pintype "passive"))
      (node (ref "C35") (pin "2") (pinfunction "2_2") (pintype "passive"))
      (node (ref "C37") (pin "2") (pinfunction "2_2") (pintype "passive"))
      (node (ref "C38") (pin "2") (pinfunction "2_2") (pintype "passive"))
      (node (ref "C41") (pin "1") (pinfunction "1_1") (pintype "passive"))
      (node (ref "C42") (pin "1") (pinfunction "1_1") (pintype "passive"))
      (node (ref "IC1") (pin "AJ7") (pinfunction "rfsn_l_RFE_2_AJ7") (pintype "passive"))
      (node (ref "IC1") (pin "AJ9") (pinfunction "rfsp_l_RFE_2_AJ9") (pintype "passive"))
      (node (ref "IC6") (pin "2") (pinfunction "GND_2") (pintype "passive"))
      (node (ref "IC7") (pin "2") (pinfunction "GND_2") (pintype "passive"))
      (node (ref "J10") (pin "2") (pinfunction "Y_2") (pintype "passive"))
      (node (ref "J6") (pin "2") (pinfunction "Y_2") (pintype "passive"))
      (node (ref "J7") (pin "2") (pinfunction "Y_2") (pintype "passive"))
      (node (ref "J8") (pin "2") (pinfunction "Y_2") (pintype "passive"))
      (node (ref "J9") (pin "2") (pinfunction "Y_2") (pintype "passive"))
      (node (ref "RA7") (pin "1") (pinfunction "1_1") (pintype "passive"))
      (node (ref "RA8") (pin "1") (pinfunction "1_1") (pintype "passive"))
      (node (ref "T10") (pin "2") (pinfunction "2_2") (pintype "passive"))
      (node (ref "T10") (pin "4") (pinfunction "4_4") (pintype "passive"))
      (node (ref "T6") (pin "2") (pinfunction "2_2") (pintype "passive"))
      (node (ref "T6") (pin "6") (pinfunction "6_6") (pintype "passive"))
      (node (ref "T7") (pin "3") (pinfunction "3_3") (pintype "passive"))
      (node (ref "T8") (pin "2") (pinfunction "2_2") (pintype "passive"))
      (node (ref "T8") (pin "4") (pinfunction "4_4") (pintype "passive"))
      (node (ref "T9") (pin "2") (pinfunction "2_2") (pintype "passive"))
      (node (ref "VT5") (pin "1") (pinfunction "S_1") (pintype "passive"))
      (node (ref "VT6") (pin "1") (pinfunction "S_1") (pintype "passive"))
    )
    (net (code "26") (name "Net-(C26-Pad2)") (class "Default")
      (node (ref "C26") (pin "2") (pinfunction "2_2") (pintype "passive"))
      (node (ref "T6") (pin "4") (pinfunction "4_4") (pintype "passive"))
    )
    (net (code "27") (name "Net-(C30-Pad2)") (class "Default")
      (node (ref "C30") (pin "2") (pinfunction "2_2") (pintype "passive"))
      (node (ref "T7") (pin "2") (pinfunction "2_2") (pintype "passive"))
    )
    (net (code "28") (name "Net-(C34-Pad2)") (class "Default")
      (node (ref "C34") (pin "2") (pinfunction "2_2") (pintype "passive"))
      (node (ref "T8") (pin "6") (pinfunction "6_6") (pintype "passive"))
    )
    (net (code "29") (name "Net-(C39-Pad2)") (class "Default")
      (node (ref "C39") (pin "2") (pinfunction "2_2") (pintype "passive"))
      (node (ref "T9") (pin "3") (pinfunction "3_3") (pintype "passive"))
    )
    (net (code "30") (name "Net-(C43-Pad2)") (class "Default")
      (node (ref "C43") (pin "2") (pinfunction "2_2") (pintype "passive"))
      (node (ref "T10") (pin "6") (pinfunction "6_6") (pintype "passive"))
    )
    (net (code "31") (name "Net-(IC6-RF_IN)") (class "Default")
      (node (ref "C30") (pin "1") (pinfunction "1_1") (pintype "passive"))
      (node (ref "IC6") (pin "5") (pinfunction "RF_IN_5") (pintype "input"))
    )
    (net (code "32") (name "Net-(IC6-RF_OUT1)") (class "Default")
      (node (ref "C29") (pin "2") (pinfunction "2_2") (pintype "passive"))
      (node (ref "IC6") (pin "1") (pinfunction "RF_OUT1_1") (pintype "output"))
    )
    (net (code "33") (name "Net-(IC6-RF_OUT2)") (class "Default")
      (node (ref "C33") (pin "1") (pinfunction "1_1") (pintype "passive"))
      (node (ref "IC6") (pin "3") (pinfunction "RF_OUT2_3") (pintype "output"))
    )
    (net (code "34") (name "Net-(IC7-RF_IN)") (class "Default")
      (node (ref "C39") (pin "1") (pinfunction "1_1") (pintype "passive"))
      (node (ref "IC7") (pin "5") (pinfunction "RF_IN_5") (pintype "input"))
    )
    (net (code "35") (name "Net-(IC7-RF_OUT1)") (class "Default")
      (node (ref "C36") (pin "2") (pinfunction "2_2") (pintype "passive"))
      (node (ref "IC7") (pin "1") (pinfunction "RF_OUT1_1") (pintype "output"))
    )
    (net (code "36") (name "Net-(IC7-RF_OUT2)") (class "Default")
      (node (ref "C40") (pin "2") (pinfunction "2_2") (pintype "passive"))
      (node (ref "IC7") (pin "3") (pinfunction "RF_OUT2_3") (pintype "output"))
    )
    (net (code "37") (name "Net-(J6-X)") (class "Default")
      (node (ref "C26") (pin "1") (pinfunction "1_1") (pintype "passive"))
      (node (ref "J6") (pin "1") (pinfunction "X_1") (pintype "passive"))
    )
    (net (code "38") (name "Net-(J7-X)") (class "Default")
      (node (ref "C29") (pin "1") (pinfunction "1_1") (pintype "passive"))
      (node (ref "J7") (pin "1") (pinfunction "X_1") (pintype "passive"))
    )
    (net (code "39") (name "Net-(J8-X)") (class "Default")
      (node (ref "C34") (pin "1") (pinfunction "1_1") (pintype "passive"))
      (node (ref "J8") (pin "1") (pinfunction "X_1") (pintype "passive"))
    )
    (net (code "40") (name "Net-(J9-X)") (class "Default")
      (node (ref "C40") (pin "1") (pinfunction "1_1") (pintype "passive"))
      (node (ref "J9") (pin "1") (pinfunction "X_1") (pintype "passive"))
    )
    (net (code "41") (name "Net-(J10-X)") (class "Default")
      (node (ref "C43") (pin "1") (pinfunction "1_1") (pintype "passive"))
      (node (ref "J10") (pin "1") (pinfunction "X_1") (pintype "passive"))
    )
    (net (code "42") (name "Net-(MN29-Pad1)") (class "Default")
      (node (ref "MN29") (pin "1") (pinfunction "1_1") (pintype "passive"))
      (node (ref "MN31") (pin "2") (pinfunction "2_2") (pintype "passive"))
    )
    (net (code "43") (name "Net-(MN30-Pad1)") (class "Default")
      (node (ref "MN30") (pin "1") (pinfunction "1_1") (pintype "passive"))
      (node (ref "MN32") (pin "2") (pinfunction "2_2") (pintype "passive"))
    )
    (net (code "44") (name "Net-(MN37-Pad1)") (class "Default")
      (node (ref "MN37") (pin "1") (pinfunction "1_1") (pintype "passive"))
      (node (ref "MN39") (pin "2") (pinfunction "2_2") (pintype "passive"))
    )
    (net (code "45") (name "Net-(MN38-Pad1)") (class "Default")
      (node (ref "MN38") (pin "1") (pinfunction "1_1") (pintype "passive"))
      (node (ref "MN40") (pin "2") (pinfunction "2_2") (pintype "passive"))
    )
    (net (code "46") (name "Net-(VT4-D)") (class "Default")
      (node (ref "RA5") (pin "2") (pinfunction "2_2") (pintype "passive"))
      (node (ref "VT4") (pin "2") (pinfunction "D_2") (pintype "passive"))
    )
    (net (code "47") (name "Net-(VT4-G1)") (class "Default")
      (node (ref "R18") (pin "1") (pinfunction "1_1") (pintype "passive"))
      (node (ref "VT4") (pin "3") (pinfunction "G2_3") (pintype "passive"))
      (node (ref "VT4") (pin "4") (pinfunction "G1_4") (pintype "passive"))
    )
    (net (code "48") (name "Net-(VT4-S)") (class "Default")
      (node (ref "C33") (pin "2") (pinfunction "2_2") (pintype "passive"))
      (node (ref "R19") (pin "1") (pinfunction "1_1") (pintype "passive"))
      (node (ref "RA6") (pin "1") (pinfunction "1_1") (pintype "passive"))
      (node (ref "RA7") (pin "2") (pinfunction "2_2") (pintype "passive"))
      (node (ref "VT4") (pin "1") (pinfunction "S_1") (pintype "passive"))
      (node (ref "VT6") (pin "2") (pinfunction "D_2") (pintype "passive"))
    )
    (net (code "49") (name "Net-(VT5-D)") (class "Default")
      (node (ref "C36") (pin "1") (pinfunction "1_1") (pintype "passive"))
      (node (ref "RA5") (pin "1") (pinfunction "1_1") (pintype "passive"))
      (node (ref "RA6") (pin "2") (pinfunction "2_2") (pintype "passive"))
      (node (ref "RA8") (pin "2") (pinfunction "2_2") (pintype "passive"))
      (node (ref "VT5") (pin "2") (pinfunction "D_2") (pintype "passive"))
    )
    (net (code "50") (name "Net-(VT5-G1)") (class "Default")
      (node (ref "R20") (pin "2") (pinfunction "2_2") (pintype "passive"))
      (node (ref "VT5") (pin "3") (pinfunction "G2_3") (pintype "passive"))
      (node (ref "VT5") (pin "4") (pinfunction "G1_4") (pintype "passive"))
    )
    (net (code "51") (name "Net-(VT6-G1)") (class "Default")
      (node (ref "R21") (pin "1") (pinfunction "1_1") (pintype "passive"))
      (node (ref "VT6") (pin "3") (pinfunction "G2_3") (pintype "passive"))
      (node (ref "VT6") (pin "4") (pinfunction "G1_4") (pintype "passive"))
    )
    (net (code "52") (name "VCC1P8_LMS") (class "Default")
      (node (ref "C24") (pin "2") (pinfunction "2_2") (pintype "passive"))
      (node (ref "C25") (pin "2") (pinfunction "2_2") (pintype "passive"))
      (node (ref "C27") (pin "2") (pinfunction "2_2") (pintype "passive"))
      (node (ref "C28") (pin "2") (pinfunction "2_2") (pintype "passive"))
      (node (ref "MN29") (pin "2") (pinfunction "2_2") (pintype "passive"))
      (node (ref "MN30") (pin "2") (pinfunction "2_2") (pintype "passive"))
      (node (ref "MN37") (pin "2") (pinfunction "2_2") (pintype "passive"))
      (node (ref "MN38") (pin "2") (pinfunction "2_2") (pintype "passive"))
      (node (ref "R19") (pin "2") (pinfunction "2_2") (pintype "passive"))
    )
  )
)
